# BIO_SENSOR.net
KiCad netlist of a schematic drawn in Altium Designer
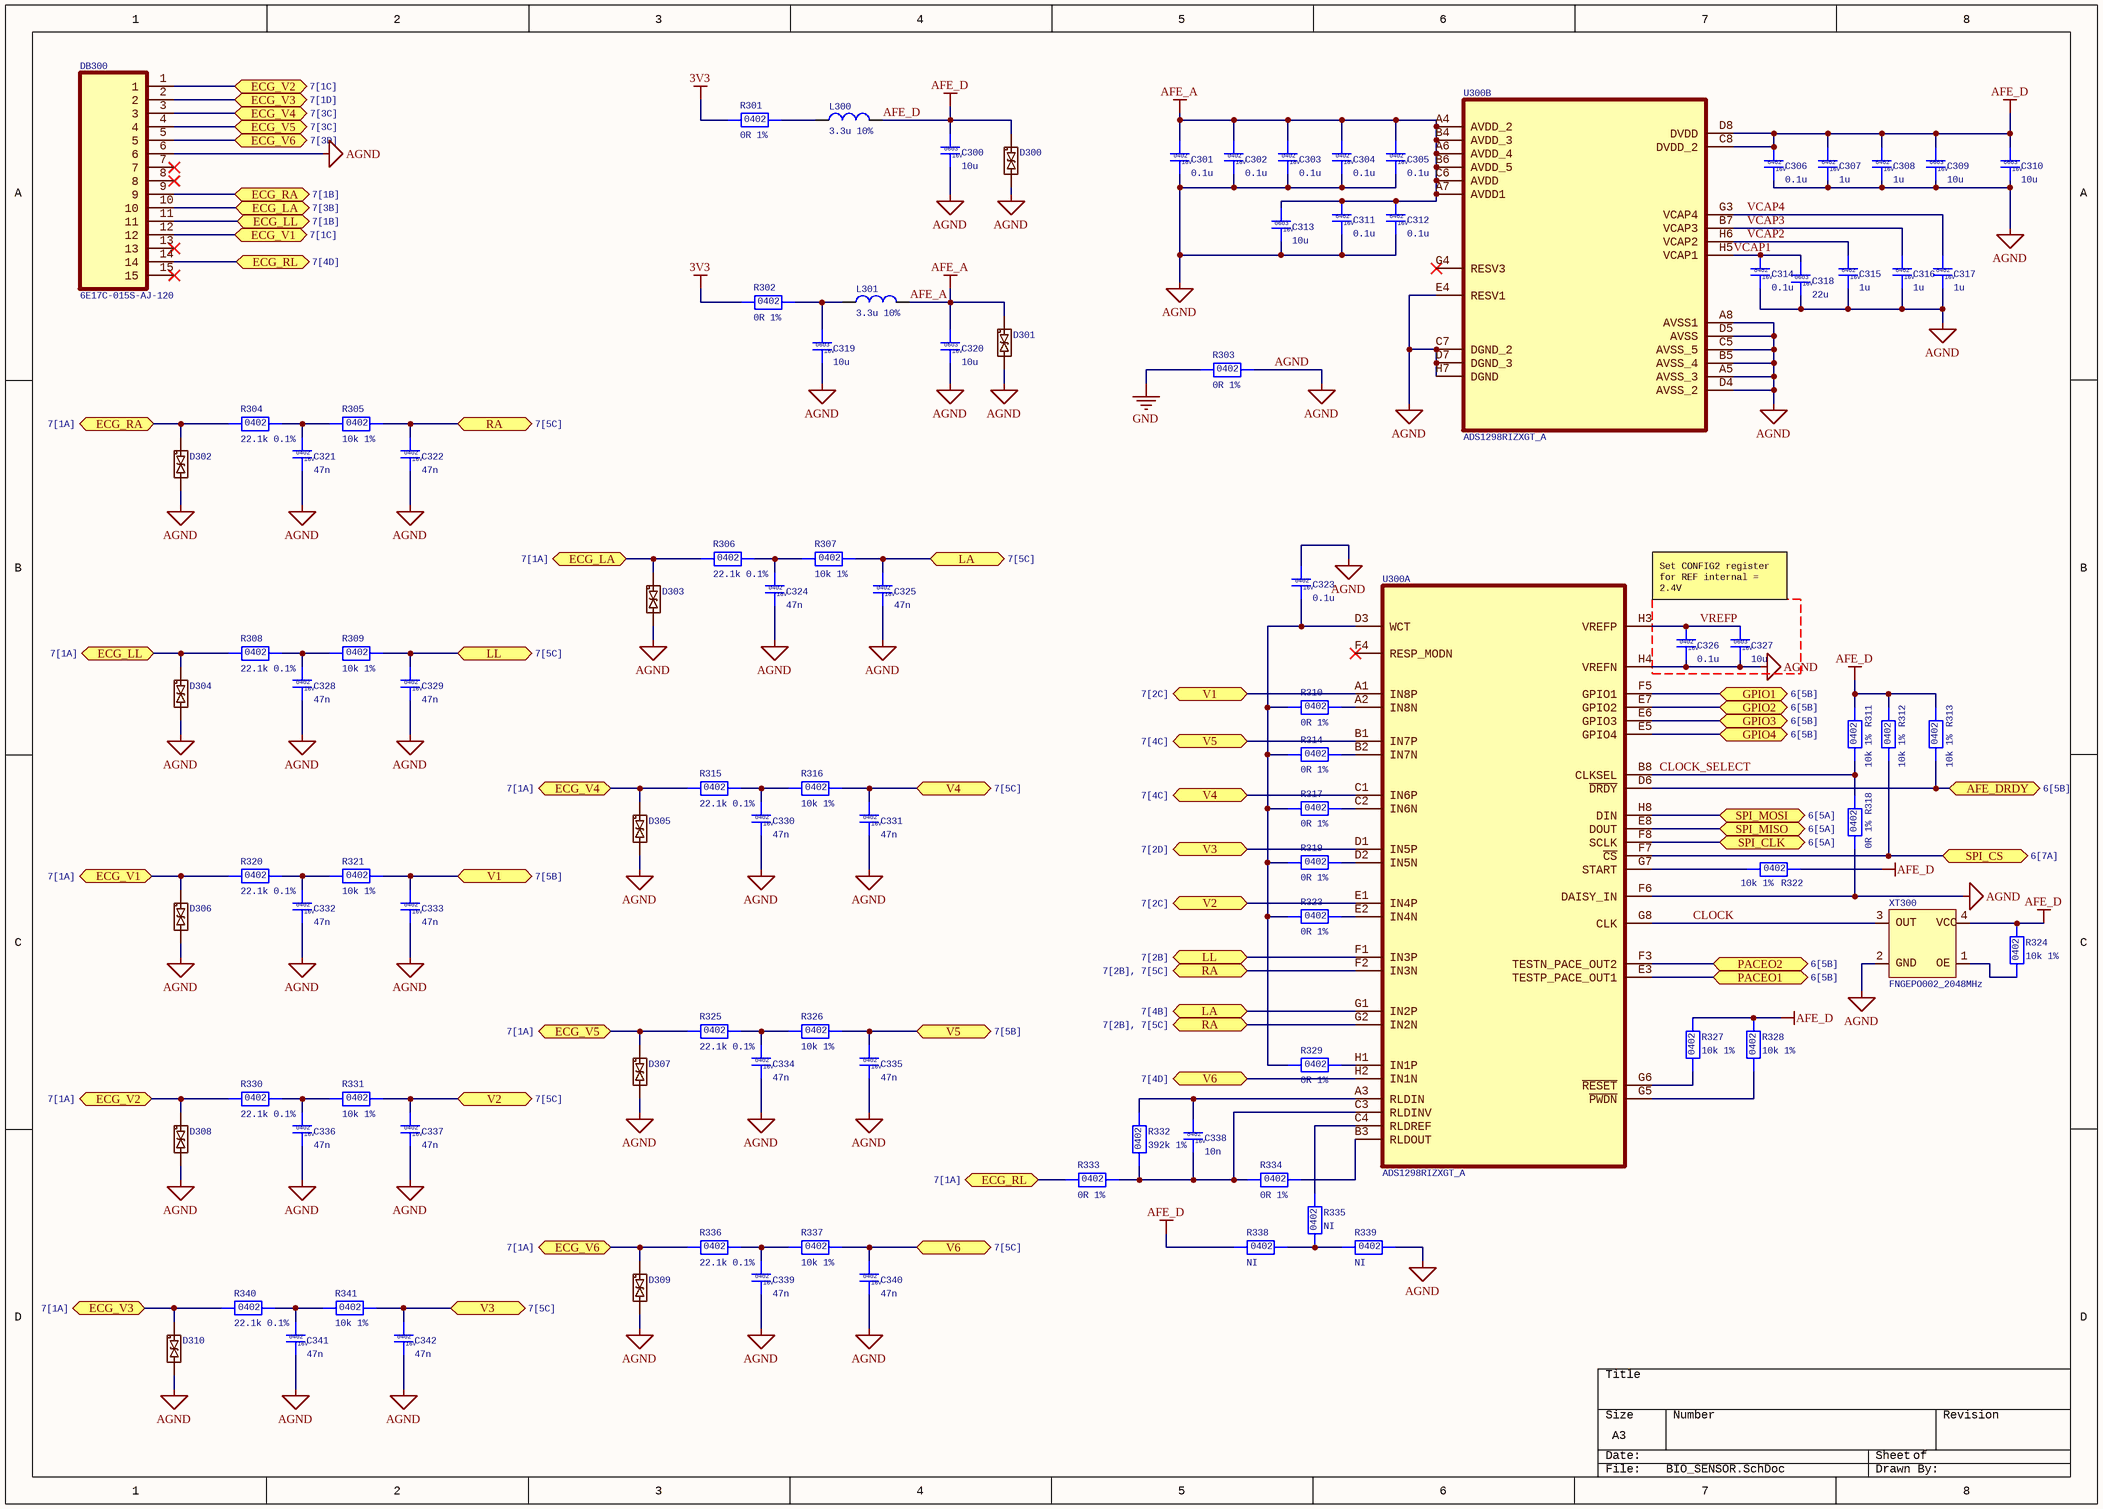
[diagram p0: BIO_SENSOR.SchDoc]

(export (version "E")
  (design (tool "Eeschema 10.0.6"))
  (components
    (comp (ref "C300")
      (value "10u")
      (footprint "CAP0603")
      (fields
        (field (name "MANUFACTURER") "Murata")
        (field (name "MANUFACTURER PART NUMBER") "GRT188R61C106ME13D")
      )
      (libsource (lib "Hw_Lib") (part "C_0402_10u"))
    )
    (comp (ref "C301")
      (value "0.1u")
      (footprint "CAP0402")
      (fields
        (field (name "MANUFACTURER") "Murata")
        (field (name "MANUFACTURER PART NUMBER") "GRM155R71C104KA88J")
      )
      (libsource (lib "Hw_Lib") (part "C_0402_0.1u"))
    )
    (comp (ref "C302")
      (value "0.1u")
      (footprint "CAP0402")
      (fields
        (field (name "MANUFACTURER") "Murata")
        (field (name "MANUFACTURER PART NUMBER") "GRM155R71C104KA88J")
      )
      (libsource (lib "Hw_Lib") (part "C_0402_0.1u"))
    )
    (comp (ref "C303")
      (value "0.1u")
      (footprint "CAP0402")
      (fields
        (field (name "MANUFACTURER") "Murata")
        (field (name "MANUFACTURER PART NUMBER") "GRM155R71C104KA88J")
      )
      (libsource (lib "Hw_Lib") (part "C_0402_0.1u"))
    )
    (comp (ref "C304")
      (value "0.1u")
      (footprint "CAP0402")
      (fields
        (field (name "MANUFACTURER") "Murata")
        (field (name "MANUFACTURER PART NUMBER") "GRM155R71C104KA88J")
      )
      (libsource (lib "Hw_Lib") (part "C_0402_0.1u"))
    )
    (comp (ref "C305")
      (value "0.1u")
      (footprint "CAP0402")
      (fields
        (field (name "MANUFACTURER") "Murata")
        (field (name "MANUFACTURER PART NUMBER") "GRM155R71C104KA88J")
      )
      (libsource (lib "Hw_Lib") (part "C_0402_0.1u"))
    )
    (comp (ref "C306")
      (value "0.1u")
      (footprint "CAP0402")
      (fields
        (field (name "MANUFACTURER") "Murata")
        (field (name "MANUFACTURER PART NUMBER") "GRM155R71C104KA88J")
      )
      (libsource (lib "Hw_Lib") (part "C_0402_0.1u"))
    )
    (comp (ref "C307")
      (value "1u")
      (footprint "CAP0402")
      (fields
        (field (name "MANUFACTURER") "Taiyo Yuden")
        (field (name "MANUFACTURER PART NUMBER") "EMK105BJ105KV-F")
      )
      (libsource (lib "Hw_Lib") (part "C_0402_1u"))
    )
    (comp (ref "C308")
      (value "1u")
      (footprint "CAP0402")
      (fields
        (field (name "MANUFACTURER") "Taiyo Yuden")
        (field (name "MANUFACTURER PART NUMBER") "EMK105BJ105KV-F")
      )
      (libsource (lib "Hw_Lib") (part "C_0402_1u"))
    )
    (comp (ref "C309")
      (value "10u")
      (footprint "CAP0603")
      (fields
        (field (name "MANUFACTURER") "Murata")
        (field (name "MANUFACTURER PART NUMBER") "GRT188R61C106ME13D")
      )
      (libsource (lib "Hw_Lib") (part "C_0402_10u"))
    )
    (comp (ref "C310")
      (value "10u")
      (footprint "CAP0603")
      (fields
        (field (name "MANUFACTURER") "Murata")
        (field (name "MANUFACTURER PART NUMBER") "GRT188R61C106ME13D")
      )
      (libsource (lib "Hw_Lib") (part "C_0402_10u"))
    )
    (comp (ref "C311")
      (value "0.1u")
      (footprint "CAP0402")
      (fields
        (field (name "MANUFACTURER") "Murata")
        (field (name "MANUFACTURER PART NUMBER") "GRM155R71C104KA88J")
      )
      (libsource (lib "Hw_Lib") (part "C_0402_0.1u"))
    )
    (comp (ref "C312")
      (value "0.1u")
      (footprint "CAP0402")
      (fields
        (field (name "MANUFACTURER") "Murata")
        (field (name "MANUFACTURER PART NUMBER") "GRM155R71C104KA88J")
      )
      (libsource (lib "Hw_Lib") (part "C_0402_0.1u"))
    )
    (comp (ref "C313")
      (value "10u")
      (footprint "CAP0603")
      (fields
        (field (name "MANUFACTURER") "Murata")
        (field (name "MANUFACTURER PART NUMBER") "GRT188R61C106ME13D")
      )
      (libsource (lib "Hw_Lib") (part "C_0402_10u"))
    )
    (comp (ref "C314")
      (value "0.1u")
      (footprint "CAP0402")
      (fields
        (field (name "MANUFACTURER") "Murata")
        (field (name "MANUFACTURER PART NUMBER") "GRM155R71C104KA88J")
      )
      (libsource (lib "Hw_Lib") (part "C_0402_0.1u"))
    )
    (comp (ref "C315")
      (value "1u")
      (footprint "CAP0402")
      (fields
        (field (name "MANUFACTURER") "Taiyo Yuden")
        (field (name "MANUFACTURER PART NUMBER") "EMK105BJ105KV-F")
      )
      (libsource (lib "Hw_Lib") (part "C_0402_1u"))
    )
    (comp (ref "C316")
      (value "1u")
      (footprint "CAP0402")
      (fields
        (field (name "MANUFACTURER") "Taiyo Yuden")
        (field (name "MANUFACTURER PART NUMBER") "EMK105BJ105KV-F")
      )
      (libsource (lib "Hw_Lib") (part "C_0402_1u"))
    )
    (comp (ref "C317")
      (value "1u")
      (footprint "CAP0402")
      (fields
        (field (name "MANUFACTURER") "Taiyo Yuden")
        (field (name "MANUFACTURER PART NUMBER") "EMK105BJ105KV-F")
      )
      (libsource (lib "Hw_Lib") (part "C_0402_1u"))
    )
    (comp (ref "C318")
      (value "22u")
      (footprint "CAP0603")
      (fields
        (field (name "MANUFACTURER") "Samsung")
        (field (name "MANUFACTURER PART NUMBER") "CL10A226MO7JZNC")
      )
      (libsource (lib "Hw_Lib") (part "C_0402_22u"))
    )
    (comp (ref "C319")
      (value "10u")
      (footprint "CAP0603")
      (fields
        (field (name "MANUFACTURER") "Murata")
        (field (name "MANUFACTURER PART NUMBER") "GRT188R61C106ME13D")
      )
      (libsource (lib "Hw_Lib") (part "C_0402_10u"))
    )
    (comp (ref "C320")
      (value "10u")
      (footprint "CAP0603")
      (fields
        (field (name "MANUFACTURER") "Murata")
        (field (name "MANUFACTURER PART NUMBER") "GRT188R61C106ME13D")
      )
      (libsource (lib "Hw_Lib") (part "C_0402_10u"))
    )
    (comp (ref "C321")
      (value "47n")
      (footprint "CAP0402")
      (fields
        (field (name "MANUFACTURER") "Murata")
        (field (name "MANUFACTURER PART NUMBER") "GCM155R71C473KA37D")
      )
      (libsource (lib "Hw_Lib") (part "C_0402_47n"))
    )
    (comp (ref "C322")
      (value "47n")
      (footprint "CAP0402")
      (fields
        (field (name "MANUFACTURER") "Murata")
        (field (name "MANUFACTURER PART NUMBER") "GCM155R71C473KA37D")
      )
      (libsource (lib "Hw_Lib") (part "C_0402_47n"))
    )
    (comp (ref "C323")
      (value "0.1u")
      (footprint "CAP0402")
      (fields
        (field (name "MANUFACTURER") "Murata")
        (field (name "MANUFACTURER PART NUMBER") "GRM155R71C104KA88J")
      )
      (libsource (lib "Hw_Lib") (part "C_0402_0.1u"))
    )
    (comp (ref "C324")
      (value "47n")
      (footprint "CAP0402")
      (fields
        (field (name "MANUFACTURER") "Murata")
        (field (name "MANUFACTURER PART NUMBER") "GCM155R71C473KA37D")
      )
      (libsource (lib "Hw_Lib") (part "C_0402_47n"))
    )
    (comp (ref "C325")
      (value "47n")
      (footprint "CAP0402")
      (fields
        (field (name "MANUFACTURER") "Murata")
        (field (name "MANUFACTURER PART NUMBER") "GCM155R71C473KA37D")
      )
      (libsource (lib "Hw_Lib") (part "C_0402_47n"))
    )
    (comp (ref "C326")
      (value "0.1u")
      (footprint "CAP0402")
      (fields
        (field (name "MANUFACTURER") "Murata")
        (field (name "MANUFACTURER PART NUMBER") "GRM155R71C104KA88J")
      )
      (libsource (lib "Hw_Lib") (part "C_0402_0.1u"))
    )
    (comp (ref "C327")
      (value "10u")
      (footprint "CAP0603")
      (fields
        (field (name "MANUFACTURER") "Murata")
        (field (name "MANUFACTURER PART NUMBER") "GRT188R61C106ME13D")
      )
      (libsource (lib "Hw_Lib") (part "C_0402_10u"))
    )
    (comp (ref "C328")
      (value "47n")
      (footprint "CAP0402")
      (fields
        (field (name "MANUFACTURER") "Murata")
        (field (name "MANUFACTURER PART NUMBER") "GCM155R71C473KA37D")
      )
      (libsource (lib "Hw_Lib") (part "C_0402_47n"))
    )
    (comp (ref "C329")
      (value "47n")
      (footprint "CAP0402")
      (fields
        (field (name "MANUFACTURER") "Murata")
        (field (name "MANUFACTURER PART NUMBER") "GCM155R71C473KA37D")
      )
      (libsource (lib "Hw_Lib") (part "C_0402_47n"))
    )
    (comp (ref "C330")
      (value "47n")
      (footprint "CAP0402")
      (fields
        (field (name "MANUFACTURER") "Murata")
        (field (name "MANUFACTURER PART NUMBER") "GCM155R71C473KA37D")
      )
      (libsource (lib "Hw_Lib") (part "C_0402_47n"))
    )
    (comp (ref "C331")
      (value "47n")
      (footprint "CAP0402")
      (fields
        (field (name "MANUFACTURER") "Murata")
        (field (name "MANUFACTURER PART NUMBER") "GCM155R71C473KA37D")
      )
      (libsource (lib "Hw_Lib") (part "C_0402_47n"))
    )
    (comp (ref "C332")
      (value "47n")
      (footprint "CAP0402")
      (fields
        (field (name "MANUFACTURER") "Murata")
        (field (name "MANUFACTURER PART NUMBER") "GCM155R71C473KA37D")
      )
      (libsource (lib "Hw_Lib") (part "C_0402_47n"))
    )
    (comp (ref "C333")
      (value "47n")
      (footprint "CAP0402")
      (fields
        (field (name "MANUFACTURER") "Murata")
        (field (name "MANUFACTURER PART NUMBER") "GCM155R71C473KA37D")
      )
      (libsource (lib "Hw_Lib") (part "C_0402_47n"))
    )
    (comp (ref "C334")
      (value "47n")
      (footprint "CAP0402")
      (fields
        (field (name "MANUFACTURER") "Murata")
        (field (name "MANUFACTURER PART NUMBER") "GCM155R71C473KA37D")
      )
      (libsource (lib "Hw_Lib") (part "C_0402_47n"))
    )
    (comp (ref "C335")
      (value "47n")
      (footprint "CAP0402")
      (fields
        (field (name "MANUFACTURER") "Murata")
        (field (name "MANUFACTURER PART NUMBER") "GCM155R71C473KA37D")
      )
      (libsource (lib "Hw_Lib") (part "C_0402_47n"))
    )
    (comp (ref "C336")
      (value "47n")
      (footprint "CAP0402")
      (fields
        (field (name "MANUFACTURER") "Murata")
        (field (name "MANUFACTURER PART NUMBER") "GCM155R71C473KA37D")
      )
      (libsource (lib "Hw_Lib") (part "C_0402_47n"))
    )
    (comp (ref "C337")
      (value "47n")
      (footprint "CAP0402")
      (fields
        (field (name "MANUFACTURER") "Murata")
        (field (name "MANUFACTURER PART NUMBER") "GCM155R71C473KA37D")
      )
      (libsource (lib "Hw_Lib") (part "C_0402_47n"))
    )
    (comp (ref "C338")
      (value "10n")
      (footprint "CAP0402")
      (fields
        (field (name "MANUFACTURER") "Murata")
        (field (name "MANUFACTURER PART NUMBER") "GRM155R71C103KA01D")
      )
      (libsource (lib "Hw_Lib") (part "C_0402_10n"))
    )
    (comp (ref "C339")
      (value "47n")
      (footprint "CAP0402")
      (fields
        (field (name "MANUFACTURER") "Murata")
        (field (name "MANUFACTURER PART NUMBER") "GCM155R71C473KA37D")
      )
      (libsource (lib "Hw_Lib") (part "C_0402_47n"))
    )
    (comp (ref "C340")
      (value "47n")
      (footprint "CAP0402")
      (fields
        (field (name "MANUFACTURER") "Murata")
        (field (name "MANUFACTURER PART NUMBER") "GCM155R71C473KA37D")
      )
      (libsource (lib "Hw_Lib") (part "C_0402_47n"))
    )
    (comp (ref "C341")
      (value "47n")
      (footprint "CAP0402")
      (fields
        (field (name "MANUFACTURER") "Murata")
        (field (name "MANUFACTURER PART NUMBER") "GCM155R71C473KA37D")
      )
      (libsource (lib "Hw_Lib") (part "C_0402_47n"))
    )
    (comp (ref "C342")
      (value "47n")
      (footprint "CAP0402")
      (fields
        (field (name "MANUFACTURER") "Murata")
        (field (name "MANUFACTURER PART NUMBER") "GCM155R71C473KA37D")
      )
      (libsource (lib "Hw_Lib") (part "C_0402_47n"))
    )
    (comp (ref "D300")
      (value "DESD3V3S1BL-7B")
      (footprint "DESD3V3S1BL-7B")
      (description "Trans Voltage Suppressor Diode, 35W, 3.3V V(RWM), Bidirectional, 1 Element, Silicon")
      (fields (field (name "MANUFACTURER") "Diodes"))
      (libsource (lib "Hw_Lib") (part "DESD3V3S1BL-7B"))
    )
    (comp (ref "D301")
      (value "DESD3V3S1BL-7B")
      (footprint "DESD3V3S1BL-7B")
      (description "Trans Voltage Suppressor Diode, 35W, 3.3V V(RWM), Bidirectional, 1 Element, Silicon")
      (fields (field (name "MANUFACTURER") "Diodes"))
      (libsource (lib "Hw_Lib") (part "DESD3V3S1BL-7B"))
    )
    (comp (ref "D302")
      (value "DESD3V3S1BL-7B")
      (footprint "DESD3V3S1BL-7B")
      (description "Trans Voltage Suppressor Diode, 35W, 3.3V V(RWM), Bidirectional, 1 Element, Silicon")
      (fields (field (name "MANUFACTURER") "Diodes"))
      (libsource (lib "Hw_Lib") (part "DESD3V3S1BL-7B"))
    )
    (comp (ref "D303")
      (value "DESD3V3S1BL-7B")
      (footprint "DESD3V3S1BL-7B")
      (description "Trans Voltage Suppressor Diode, 35W, 3.3V V(RWM), Bidirectional, 1 Element, Silicon")
      (fields (field (name "MANUFACTURER") "Diodes"))
      (libsource (lib "Hw_Lib") (part "DESD3V3S1BL-7B"))
    )
    (comp (ref "D304")
      (value "DESD3V3S1BL-7B")
      (footprint "DESD3V3S1BL-7B")
      (description "Trans Voltage Suppressor Diode, 35W, 3.3V V(RWM), Bidirectional, 1 Element, Silicon")
      (fields (field (name "MANUFACTURER") "Diodes"))
      (libsource (lib "Hw_Lib") (part "DESD3V3S1BL-7B"))
    )
    (comp (ref "D305")
      (value "DESD3V3S1BL-7B")
      (footprint "DESD3V3S1BL-7B")
      (description "Trans Voltage Suppressor Diode, 35W, 3.3V V(RWM), Bidirectional, 1 Element, Silicon")
      (fields (field (name "MANUFACTURER") "Diodes"))
      (libsource (lib "Hw_Lib") (part "DESD3V3S1BL-7B"))
    )
    (comp (ref "D306")
      (value "DESD3V3S1BL-7B")
      (footprint "DESD3V3S1BL-7B")
      (description "Trans Voltage Suppressor Diode, 35W, 3.3V V(RWM), Bidirectional, 1 Element, Silicon")
      (fields (field (name "MANUFACTURER") "Diodes"))
      (libsource (lib "Hw_Lib") (part "DESD3V3S1BL-7B"))
    )
    (comp (ref "D307")
      (value "DESD3V3S1BL-7B")
      (footprint "DESD3V3S1BL-7B")
      (description "Trans Voltage Suppressor Diode, 35W, 3.3V V(RWM), Bidirectional, 1 Element, Silicon")
      (fields (field (name "MANUFACTURER") "Diodes"))
      (libsource (lib "Hw_Lib") (part "DESD3V3S1BL-7B"))
    )
    (comp (ref "D308")
      (value "DESD3V3S1BL-7B")
      (footprint "DESD3V3S1BL-7B")
      (description "Trans Voltage Suppressor Diode, 35W, 3.3V V(RWM), Bidirectional, 1 Element, Silicon")
      (fields (field (name "MANUFACTURER") "Diodes"))
      (libsource (lib "Hw_Lib") (part "DESD3V3S1BL-7B"))
    )
    (comp (ref "D309")
      (value "DESD3V3S1BL-7B")
      (footprint "DESD3V3S1BL-7B")
      (description "Trans Voltage Suppressor Diode, 35W, 3.3V V(RWM), Bidirectional, 1 Element, Silicon")
      (fields (field (name "MANUFACTURER") "Diodes"))
      (libsource (lib "Hw_Lib") (part "DESD3V3S1BL-7B"))
    )
    (comp (ref "D310")
      (value "DESD3V3S1BL-7B")
      (footprint "DESD3V3S1BL-7B")
      (description "Trans Voltage Suppressor Diode, 35W, 3.3V V(RWM), Bidirectional, 1 Element, Silicon")
      (fields (field (name "MANUFACTURER") "Diodes"))
      (libsource (lib "Hw_Lib") (part "DESD3V3S1BL-7B"))
    )
    (comp (ref "DB300")
      (value "6E17C-015S-AJ-120")
      (footprint "6E17C-015S-AJ-120")
      (description "Conn D-Subminiature SKT 15 POS 2.74mm Solder RA Thru-Hole 15 Terminal 1 Port")
      (fields
        (field (name "MANUFACTURER") "Amphenol Communications Solutions")
        (field (name "MANUFACTURER PART NUMBER") "6E17C015SAJ120")
      )
      (libsource (lib "Hw_Lib") (part "6E17C-015S-AJ-120"))
    )
    (comp (ref "L300")
      (value "3.3u 10%")
      (footprint "0402(1005)")
      (description "General Purpose Inductor, 2.7uH, 10%, 1 Element, Ferrite-Core, SMD, 0402")
      (fields
        (field (name "MANUFACTURER") "Abracon")
        (field (name "MANUFACTURER PART NUMBER") "AIML-0402-2R7K-T")
      )
      (libsource (lib "Hw_Lib") (part "Inductor 3.3u"))
    )
    (comp (ref "L301")
      (value "3.3u 10%")
      (footprint "0402(1005)")
      (description "General Purpose Inductor, 2.7uH, 10%, 1 Element, Ferrite-Core, SMD, 0402")
      (fields
        (field (name "MANUFACTURER") "Abracon")
        (field (name "MANUFACTURER PART NUMBER") "AIML-0402-2R7K-T")
      )
      (libsource (lib "Hw_Lib") (part "Inductor 3.3u"))
    )
    (comp (ref "R301")
      (value "0R 1%")
      (footprint "RES0402")
      (description "Metal Glaze/thick Film, 0.0625W, 0ohm, Surface Mount, 0402")
      (fields
        (field (name "MANUFACTURER") "Yageo")
        (field (name "MANUFACTURER PART NUMBER") "RC0402JR-070RL")
      )
      (libsource (lib "Hw_Lib") (part "R_0402_0R"))
    )
    (comp (ref "R302")
      (value "0R 1%")
      (footprint "RES0402")
      (description "Metal Glaze/thick Film, 0.0625W, 0ohm, Surface Mount, 0402")
      (fields
        (field (name "MANUFACTURER") "Yageo")
        (field (name "MANUFACTURER PART NUMBER") "RC0402JR-070RL")
      )
      (libsource (lib "Hw_Lib") (part "R_0402_0R"))
    )
    (comp (ref "R303")
      (value "0R 1%")
      (footprint "RES0402")
      (description "Metal Glaze/thick Film, 0.0625W, 0ohm, Surface Mount, 0402")
      (fields
        (field (name "MANUFACTURER") "Yageo")
        (field (name "MANUFACTURER PART NUMBER") "RC0402JR-070RL")
      )
      (libsource (lib "Hw_Lib") (part "R_0402_0R"))
    )
    (comp (ref "R304")
      (value "22.1k 0.1%")
      (footprint "R0402")
      (description "Fixed Resistor, Thin Film, 0.063W, 22100ohm, 50V, 0.1% +/-Tol, 25ppm/Cel, Surface Mount, 0402")
      (fields
        (field (name "MANUFACTURER") "Vishay Dale")
        (field (name "MANUFACTURER PART NUMBER") "TNPW040222K1BEED")
      )
      (libsource (lib "Hw_Lib") (part "R_0402_22.1k"))
    )
    (comp (ref "R305")
      (value "10k 1%")
      (footprint "R0402")
      (fields
        (field (name "MANUFACTURER") "Samsung")
        (field (name "MANUFACTURER PART NUMBER") "RC1005F103CS")
        (field (name "TOLERANCE") "1%")
      )
      (libsource (lib "Hw_Lib") (part "R_0402_10k"))
    )
    (comp (ref "R306")
      (value "22.1k 0.1%")
      (footprint "R0402")
      (description "Fixed Resistor, Thin Film, 0.063W, 22100ohm, 50V, 0.1% +/-Tol, 25ppm/Cel, Surface Mount, 0402")
      (fields
        (field (name "MANUFACTURER") "Vishay Dale")
        (field (name "MANUFACTURER PART NUMBER") "TNPW040222K1BEED")
      )
      (libsource (lib "Hw_Lib") (part "R_0402_22.1k"))
    )
    (comp (ref "R307")
      (value "10k 1%")
      (footprint "R0402")
      (fields
        (field (name "MANUFACTURER") "Samsung")
        (field (name "MANUFACTURER PART NUMBER") "RC1005F103CS")
        (field (name "TOLERANCE") "1%")
      )
      (libsource (lib "Hw_Lib") (part "R_0402_10k"))
    )
    (comp (ref "R308")
      (value "22.1k 0.1%")
      (footprint "R0402")
      (description "Fixed Resistor, Thin Film, 0.063W, 22100ohm, 50V, 0.1% +/-Tol, 25ppm/Cel, Surface Mount, 0402")
      (fields
        (field (name "MANUFACTURER") "Vishay Dale")
        (field (name "MANUFACTURER PART NUMBER") "TNPW040222K1BEED")
      )
      (libsource (lib "Hw_Lib") (part "R_0402_22.1k"))
    )
    (comp (ref "R309")
      (value "10k 1%")
      (footprint "R0402")
      (fields
        (field (name "MANUFACTURER") "Samsung")
        (field (name "MANUFACTURER PART NUMBER") "RC1005F103CS")
        (field (name "TOLERANCE") "1%")
      )
      (libsource (lib "Hw_Lib") (part "R_0402_10k"))
    )
    (comp (ref "R310")
      (value "0R 1%")
      (footprint "RES0402")
      (description "Metal Glaze/thick Film, 0.0625W, 0ohm, Surface Mount, 0402")
      (fields
        (field (name "MANUFACTURER") "Yageo")
        (field (name "MANUFACTURER PART NUMBER") "RC0402JR-070RL")
      )
      (libsource (lib "Hw_Lib") (part "R_0402_0R"))
    )
    (comp (ref "R311")
      (value "10k 1%")
      (footprint "R0402")
      (fields
        (field (name "MANUFACTURER") "Samsung")
        (field (name "MANUFACTURER PART NUMBER") "RC1005F103CS")
        (field (name "TOLERANCE") "1%")
      )
      (libsource (lib "Hw_Lib") (part "R_0402_10k"))
    )
    (comp (ref "R312")
      (value "10k 1%")
      (footprint "R0402")
      (fields
        (field (name "MANUFACTURER") "Samsung")
        (field (name "MANUFACTURER PART NUMBER") "RC1005F103CS")
        (field (name "TOLERANCE") "1%")
      )
      (libsource (lib "Hw_Lib") (part "R_0402_10k"))
    )
    (comp (ref "R313")
      (value "10k 1%")
      (footprint "R0402")
      (fields
        (field (name "MANUFACTURER") "Samsung")
        (field (name "MANUFACTURER PART NUMBER") "RC1005F103CS")
        (field (name "TOLERANCE") "1%")
      )
      (libsource (lib "Hw_Lib") (part "R_0402_10k"))
    )
    (comp (ref "R314")
      (value "0R 1%")
      (footprint "RES0402")
      (description "Metal Glaze/thick Film, 0.0625W, 0ohm, Surface Mount, 0402")
      (fields
        (field (name "MANUFACTURER") "Yageo")
        (field (name "MANUFACTURER PART NUMBER") "RC0402JR-070RL")
      )
      (libsource (lib "Hw_Lib") (part "R_0402_0R"))
    )
    (comp (ref "R315")
      (value "22.1k 0.1%")
      (footprint "R0402")
      (description "Fixed Resistor, Thin Film, 0.063W, 22100ohm, 50V, 0.1% +/-Tol, 25ppm/Cel, Surface Mount, 0402")
      (fields
        (field (name "MANUFACTURER") "Vishay Dale")
        (field (name "MANUFACTURER PART NUMBER") "TNPW040222K1BEED")
      )
      (libsource (lib "Hw_Lib") (part "R_0402_22.1k"))
    )
    (comp (ref "R316")
      (value "10k 1%")
      (footprint "R0402")
      (fields
        (field (name "MANUFACTURER") "Samsung")
        (field (name "MANUFACTURER PART NUMBER") "RC1005F103CS")
        (field (name "TOLERANCE") "1%")
      )
      (libsource (lib "Hw_Lib") (part "R_0402_10k"))
    )
    (comp (ref "R317")
      (value "0R 1%")
      (footprint "RES0402")
      (description "Metal Glaze/thick Film, 0.0625W, 0ohm, Surface Mount, 0402")
      (fields
        (field (name "MANUFACTURER") "Yageo")
        (field (name "MANUFACTURER PART NUMBER") "RC0402JR-070RL")
      )
      (libsource (lib "Hw_Lib") (part "R_0402_0R"))
    )
    (comp (ref "R318")
      (value "0R 1%")
      (footprint "RES0402")
      (description "Metal Glaze/thick Film, 0.0625W, 0ohm, Surface Mount, 0402")
      (fields
        (field (name "MANUFACTURER") "Yageo")
        (field (name "MANUFACTURER PART NUMBER") "RC0402JR-070RL")
      )
      (libsource (lib "Hw_Lib") (part "R_0402_0R"))
    )
    (comp (ref "R319")
      (value "0R 1%")
      (footprint "RES0402")
      (description "Metal Glaze/thick Film, 0.0625W, 0ohm, Surface Mount, 0402")
      (fields
        (field (name "MANUFACTURER") "Yageo")
        (field (name "MANUFACTURER PART NUMBER") "RC0402JR-070RL")
      )
      (libsource (lib "Hw_Lib") (part "R_0402_0R"))
    )
    (comp (ref "R320")
      (value "22.1k 0.1%")
      (footprint "R0402")
      (description "Fixed Resistor, Thin Film, 0.063W, 22100ohm, 50V, 0.1% +/-Tol, 25ppm/Cel, Surface Mount, 0402")
      (fields
        (field (name "MANUFACTURER") "Vishay Dale")
        (field (name "MANUFACTURER PART NUMBER") "TNPW040222K1BEED")
      )
      (libsource (lib "Hw_Lib") (part "R_0402_22.1k"))
    )
    (comp (ref "R321")
      (value "10k 1%")
      (footprint "R0402")
      (fields
        (field (name "MANUFACTURER") "Samsung")
        (field (name "MANUFACTURER PART NUMBER") "RC1005F103CS")
        (field (name "TOLERANCE") "1%")
      )
      (libsource (lib "Hw_Lib") (part "R_0402_10k"))
    )
    (comp (ref "R322")
      (value "10k 1%")
      (footprint "R0402")
      (fields
        (field (name "MANUFACTURER") "Samsung")
        (field (name "MANUFACTURER PART NUMBER") "RC1005F103CS")
        (field (name "TOLERANCE") "1%")
      )
      (libsource (lib "Hw_Lib") (part "R_0402_10k"))
    )
    (comp (ref "R323")
      (value "0R 1%")
      (footprint "RES0402")
      (description "Metal Glaze/thick Film, 0.0625W, 0ohm, Surface Mount, 0402")
      (fields
        (field (name "MANUFACTURER") "Yageo")
        (field (name "MANUFACTURER PART NUMBER") "RC0402JR-070RL")
      )
      (libsource (lib "Hw_Lib") (part "R_0402_0R"))
    )
    (comp (ref "R324")
      (value "10k 1%")
      (footprint "R0402")
      (fields
        (field (name "MANUFACTURER") "Samsung")
        (field (name "MANUFACTURER PART NUMBER") "RC1005F103CS")
        (field (name "TOLERANCE") "1%")
      )
      (libsource (lib "Hw_Lib") (part "R_0402_10k"))
    )
    (comp (ref "R325")
      (value "22.1k 0.1%")
      (footprint "R0402")
      (description "Fixed Resistor, Thin Film, 0.063W, 22100ohm, 50V, 0.1% +/-Tol, 25ppm/Cel, Surface Mount, 0402")
      (fields
        (field (name "MANUFACTURER") "Vishay Dale")
        (field (name "MANUFACTURER PART NUMBER") "TNPW040222K1BEED")
      )
      (libsource (lib "Hw_Lib") (part "R_0402_22.1k"))
    )
    (comp (ref "R326")
      (value "10k 1%")
      (footprint "R0402")
      (fields
        (field (name "MANUFACTURER") "Samsung")
        (field (name "MANUFACTURER PART NUMBER") "RC1005F103CS")
        (field (name "TOLERANCE") "1%")
      )
      (libsource (lib "Hw_Lib") (part "R_0402_10k"))
    )
    (comp (ref "R327")
      (value "10k 1%")
      (footprint "R0402")
      (fields
        (field (name "MANUFACTURER") "Samsung")
        (field (name "MANUFACTURER PART NUMBER") "RC1005F103CS")
        (field (name "TOLERANCE") "1%")
      )
      (libsource (lib "Hw_Lib") (part "R_0402_10k"))
    )
    (comp (ref "R328")
      (value "10k 1%")
      (footprint "R0402")
      (fields
        (field (name "MANUFACTURER") "Samsung")
        (field (name "MANUFACTURER PART NUMBER") "RC1005F103CS")
        (field (name "TOLERANCE") "1%")
      )
      (libsource (lib "Hw_Lib") (part "R_0402_10k"))
    )
    (comp (ref "R329")
      (value "0R 1%")
      (footprint "RES0402")
      (description "Metal Glaze/thick Film, 0.0625W, 0ohm, Surface Mount, 0402")
      (fields
        (field (name "MANUFACTURER") "Yageo")
        (field (name "MANUFACTURER PART NUMBER") "RC0402JR-070RL")
      )
      (libsource (lib "Hw_Lib") (part "R_0402_0R"))
    )
    (comp (ref "R330")
      (value "22.1k 0.1%")
      (footprint "R0402")
      (description "Fixed Resistor, Thin Film, 0.063W, 22100ohm, 50V, 0.1% +/-Tol, 25ppm/Cel, Surface Mount, 0402")
      (fields
        (field (name "MANUFACTURER") "Vishay Dale")
        (field (name "MANUFACTURER PART NUMBER") "TNPW040222K1BEED")
      )
      (libsource (lib "Hw_Lib") (part "R_0402_22.1k"))
    )
    (comp (ref "R331")
      (value "10k 1%")
      (footprint "R0402")
      (fields
        (field (name "MANUFACTURER") "Samsung")
        (field (name "MANUFACTURER PART NUMBER") "RC1005F103CS")
        (field (name "TOLERANCE") "1%")
      )
      (libsource (lib "Hw_Lib") (part "R_0402_10k"))
    )
    (comp (ref "R332")
      (value "392k 1%")
      (footprint "R0402")
      (fields
        (field (name "MANUFACTURER") "KOA Speer")
        (field (name "MANUFACTURER PART NUMBER") "RK73H1ETTP3923F")
        (field (name "TOLERANCE") "1%")
      )
      (libsource (lib "Hw_Lib") (part "R_0402_392k"))
    )
    (comp (ref "R333")
      (value "0R 1%")
      (footprint "RES0402")
      (description "Metal Glaze/thick Film, 0.0625W, 0ohm, Surface Mount, 0402")
      (fields
        (field (name "MANUFACTURER") "Yageo")
        (field (name "MANUFACTURER PART NUMBER") "RC0402JR-070RL")
      )
      (libsource (lib "Hw_Lib") (part "R_0402_0R"))
    )
    (comp (ref "R334")
      (value "0R 1%")
      (footprint "RES0402")
      (description "Metal Glaze/thick Film, 0.0625W, 0ohm, Surface Mount, 0402")
      (fields
        (field (name "MANUFACTURER") "Yageo")
        (field (name "MANUFACTURER PART NUMBER") "RC0402JR-070RL")
      )
      (libsource (lib "Hw_Lib") (part "R_0402_0R"))
    )
    (comp (ref "R335")
      (value "NI")
      (footprint "RES0402")
      (description "Metal Glaze/thick Film, 0.0625W, 0ohm, Surface Mount, 0402")
      (fields
        (field (name "MANUFACTURER") "Yageo")
        (field (name "MANUFACTURER PART NUMBER") "RC0402JR-070RL")
      )
      (libsource (lib "Hw_Lib") (part "R_0402_0R"))
    )
    (comp (ref "R336")
      (value "22.1k 0.1%")
      (footprint "R0402")
      (description "Fixed Resistor, Thin Film, 0.063W, 22100ohm, 50V, 0.1% +/-Tol, 25ppm/Cel, Surface Mount, 0402")
      (fields
        (field (name "MANUFACTURER") "Vishay Dale")
        (field (name "MANUFACTURER PART NUMBER") "TNPW040222K1BEED")
      )
      (libsource (lib "Hw_Lib") (part "R_0402_22.1k"))
    )
    (comp (ref "R337")
      (value "10k 1%")
      (footprint "R0402")
      (fields
        (field (name "MANUFACTURER") "Samsung")
        (field (name "MANUFACTURER PART NUMBER") "RC1005F103CS")
        (field (name "TOLERANCE") "1%")
      )
      (libsource (lib "Hw_Lib") (part "R_0402_10k"))
    )
    (comp (ref "R338")
      (value "NI")
      (footprint "RES0402")
      (description "Metal Glaze/thick Film, 0.0625W, 0ohm, Surface Mount, 0402")
      (fields
        (field (name "MANUFACTURER") "Yageo")
        (field (name "MANUFACTURER PART NUMBER") "RC0402JR-070RL")
      )
      (libsource (lib "Hw_Lib") (part "R_0402_0R"))
    )
    (comp (ref "R339")
      (value "NI")
      (footprint "RES0402")
      (description "Metal Glaze/thick Film, 0.0625W, 0ohm, Surface Mount, 0402")
      (fields
        (field (name "MANUFACTURER") "Yageo")
        (field (name "MANUFACTURER PART NUMBER") "RC0402JR-070RL")
      )
      (libsource (lib "Hw_Lib") (part "R_0402_0R"))
    )
    (comp (ref "R340")
      (value "22.1k 0.1%")
      (footprint "R0402")
      (description "Fixed Resistor, Thin Film, 0.063W, 22100ohm, 50V, 0.1% +/-Tol, 25ppm/Cel, Surface Mount, 0402")
      (fields
        (field (name "MANUFACTURER") "Vishay Dale")
        (field (name "MANUFACTURER PART NUMBER") "TNPW040222K1BEED")
      )
      (libsource (lib "Hw_Lib") (part "R_0402_22.1k"))
    )
    (comp (ref "R341")
      (value "10k 1%")
      (footprint "R0402")
      (fields
        (field (name "MANUFACTURER") "Samsung")
        (field (name "MANUFACTURER PART NUMBER") "RC1005F103CS")
        (field (name "TOLERANCE") "1%")
      )
      (libsource (lib "Hw_Lib") (part "R_0402_10k"))
    )
    (comp (ref "U300")
      (value "ADS1298RIZXGT_A")
      (footprint "ADS1298RIZXGT")
      (description "Analog Circuit, 1 Func, 8 Channel, PBGA64")
      (fields
        (field (name "MANUFACTURER") "Texas Instruments")
        (field (name "MANUFACTURER PART NUMBER") "ADS1298RIZXGT")
      )
      (libsource (lib "Hw_Lib") (part "ADS1298RIZXGT_A"))
    )
    (comp (ref "XT300")
      (value "FNGEPO002_2048MHz")
      (footprint "FNGEPO002")
      (description "CMOS Output Clock Oscillator, 2.048MHz Nom")
      (fields (field (name "MANUFACTURER") "Diodes") (field (name "MANUFACTURER PART NUMBER") "FNGEPO002"))
      (libsource (lib "Hw_Lib") (part "FNGEPO002_2048MHz"))
    )
  )
  (nets
    (net (code "2") (name "/AFE_DRDY") (class "Default")
      (node (ref "R313") (pin "1") (pinfunction "1_1") (pintype "passive"))
      (node (ref "U300") (pin "D6") (pinfunction "~{DRDY}_D6") (pintype "open_collector"))
    )
    (net (code "3") (name "/CLOCK") (class "Default")
      (node (ref "U300") (pin "G8") (pinfunction "CLK_G8") (pintype "open_collector"))
      (node (ref "XT300") (pin "3") (pinfunction "OUT_3") (pintype "passive"))
    )
    (net (code "4") (name "/CLOCK_SELECT") (class "Default")
      (node (ref "R311") (pin "1") (pinfunction "1_1") (pintype "passive"))
      (node (ref "R318") (pin "2") (pinfunction "2_2") (pintype "passive"))
      (node (ref "U300") (pin "B8") (pinfunction "CLKSEL_B8") (pintype "open_collector"))
    )
    (net (code "5") (name "/ECG_LA") (class "Default")
      (node (ref "D303") (pin "1") (pinfunction "1_1") (pintype "passive"))
      (node (ref "DB300") (pin "10") (pinfunction "10_10") (pintype "passive"))
      (node (ref "R306") (pin "1") (pinfunction "1_1") (pintype "passive"))
    )
    (net (code "6") (name "/ECG_LL") (class "Default")
      (node (ref "D304") (pin "1") (pinfunction "1_1") (pintype "passive"))
      (node (ref "DB300") (pin "11") (pinfunction "11_11") (pintype "passive"))
      (node (ref "R308") (pin "1") (pinfunction "1_1") (pintype "passive"))
    )
    (net (code "7") (name "/ECG_RA") (class "Default")
      (node (ref "D302") (pin "1") (pinfunction "1_1") (pintype "passive"))
      (node (ref "DB300") (pin "9") (pinfunction "9_9") (pintype "passive"))
      (node (ref "R304") (pin "1") (pinfunction "1_1") (pintype "passive"))
    )
    (net (code "8") (name "/ECG_RL") (class "Default")
      (node (ref "DB300") (pin "14") (pinfunction "14_14") (pintype "passive"))
      (node (ref "R333") (pin "1") (pinfunction "1_1") (pintype "passive"))
    )
    (net (code "9") (name "/ECG_V1") (class "Default")
      (node (ref "D306") (pin "1") (pinfunction "1_1") (pintype "passive"))
      (node (ref "DB300") (pin "12") (pinfunction "12_12") (pintype "passive"))
      (node (ref "R320") (pin "1") (pinfunction "1_1") (pintype "passive"))
    )
    (net (code "10") (name "/ECG_V2") (class "Default")
      (node (ref "D308") (pin "1") (pinfunction "1_1") (pintype "passive"))
      (node (ref "DB300") (pin "1") (pinfunction "1_1") (pintype "passive"))
      (node (ref "R330") (pin "1") (pinfunction "1_1") (pintype "passive"))
    )
    (net (code "11") (name "/ECG_V3") (class "Default")
      (node (ref "D310") (pin "1") (pinfunction "1_1") (pintype "passive"))
      (node (ref "DB300") (pin "2") (pinfunction "2_2") (pintype "passive"))
      (node (ref "R340") (pin "1") (pinfunction "1_1") (pintype "passive"))
    )
    (net (code "12") (name "/ECG_V4") (class "Default")
      (node (ref "D305") (pin "1") (pinfunction "1_1") (pintype "passive"))
      (node (ref "DB300") (pin "3") (pinfunction "3_3") (pintype "passive"))
      (node (ref "R315") (pin "1") (pinfunction "1_1") (pintype "passive"))
    )
    (net (code "13") (name "/ECG_V5") (class "Default")
      (node (ref "D307") (pin "1") (pinfunction "1_1") (pintype "passive"))
      (node (ref "DB300") (pin "4") (pinfunction "4_4") (pintype "passive"))
      (node (ref "R325") (pin "1") (pinfunction "1_1") (pintype "passive"))
    )
    (net (code "14") (name "/ECG_V6") (class "Default")
      (node (ref "D309") (pin "1") (pinfunction "1_1") (pintype "passive"))
      (node (ref "DB300") (pin "5") (pinfunction "5_5") (pintype "passive"))
      (node (ref "R336") (pin "1") (pinfunction "1_1") (pintype "passive"))
    )
    (net (code "15") (name "/GPIO1") (class "Default")
      (node (ref "U300") (pin "F5") (pinfunction "GPIO1_F5") (pintype "open_collector"))
    )
    (net (code "16") (name "/GPIO2") (class "Default")
      (node (ref "U300") (pin "E7") (pinfunction "GPIO2_E7") (pintype "open_collector"))
    )
    (net (code "17") (name "/GPIO3") (class "Default")
      (node (ref "U300") (pin "E6") (pinfunction "GPIO3_E6") (pintype "open_collector"))
    )
    (net (code "18") (name "/GPIO4") (class "Default")
      (node (ref "U300") (pin "E5") (pinfunction "GPIO4_E5") (pintype "open_collector"))
    )
    (net (code "19") (name "/LA") (class "Default")
      (node (ref "C325") (pin "1") (pinfunction "1_1") (pintype "passive"))
      (node (ref "R307") (pin "2") (pinfunction "2_2") (pintype "passive"))
      (node (ref "U300") (pin "G1") (pinfunction "IN2P_G1") (pintype "open_collector"))
    )
    (net (code "20") (name "/LL") (class "Default")
      (node (ref "C329") (pin "1") (pinfunction "1_1") (pintype "passive"))
      (node (ref "R309") (pin "2") (pinfunction "2_2") (pintype "passive"))
      (node (ref "U300") (pin "F1") (pinfunction "IN3P_F1") (pintype "open_collector"))
    )
    (net (code "21") (name "/PACEO1") (class "Default")
      (node (ref "U300") (pin "E3") (pinfunction "TESTP_PACE_OUT1_E3") (pintype "open_collector"))
    )
    (net (code "22") (name "/PACEO2") (class "Default")
      (node (ref "U300") (pin "F3") (pinfunction "TESTN_PACE_OUT2_F3") (pintype "open_collector"))
    )
    (net (code "23") (name "/RA") (class "Default")
      (node (ref "C322") (pin "1") (pinfunction "1_1") (pintype "passive"))
      (node (ref "R305") (pin "2") (pinfunction "2_2") (pintype "passive"))
      (node (ref "U300") (pin "F2") (pinfunction "IN3N_F2") (pintype "open_collector"))
      (node (ref "U300") (pin "G2") (pinfunction "IN2N_G2") (pintype "open_collector"))
    )
    (net (code "24") (name "/SPI_CLK") (class "Default")
      (node (ref "U300") (pin "F8") (pinfunction "SCLK_F8") (pintype "open_collector"))
    )
    (net (code "25") (name "/SPI_CS") (class "Default")
      (node (ref "R312") (pin "1") (pinfunction "1_1") (pintype "passive"))
      (node (ref "U300") (pin "F7") (pinfunction "~{CS}_F7") (pintype "open_collector"))
    )
    (net (code "26") (name "/SPI_MISO") (class "Default")
      (node (ref "U300") (pin "E8") (pinfunction "DOUT_E8") (pintype "open_collector"))
    )
    (net (code "27") (name "/SPI_MOSI") (class "Default")
      (node (ref "U300") (pin "H8") (pinfunction "DIN_H8") (pintype "open_collector"))
    )
    (net (code "28") (name "/V1") (class "Default")
      (node (ref "C333") (pin "1") (pinfunction "1_1") (pintype "passive"))
      (node (ref "R321") (pin "2") (pinfunction "2_2") (pintype "passive"))
      (node (ref "U300") (pin "A1") (pinfunction "IN8P_A1") (pintype "open_collector"))
    )
    (net (code "29") (name "/V2") (class "Default")
      (node (ref "C337") (pin "1") (pinfunction "1_1") (pintype "passive"))
      (node (ref "R331") (pin "2") (pinfunction "2_2") (pintype "passive"))
      (node (ref "U300") (pin "E1") (pinfunction "IN4P_E1") (pintype "open_collector"))
    )
    (net (code "30") (name "/V3") (class "Default")
      (node (ref "C342") (pin "1") (pinfunction "1_1") (pintype "passive"))
      (node (ref "R341") (pin "2") (pinfunction "2_2") (pintype "passive"))
      (node (ref "U300") (pin "D1") (pinfunction "IN5P_D1") (pintype "open_collector"))
    )
    (net (code "31") (name "/V4") (class "Default")
      (node (ref "C331") (pin "1") (pinfunction "1_1") (pintype "passive"))
      (node (ref "R316") (pin "2") (pinfunction "2_2") (pintype "passive"))
      (node (ref "U300") (pin "C1") (pinfunction "IN6P_C1") (pintype "open_collector"))
    )
    (net (code "32") (name "/V5") (class "Default")
      (node (ref "C335") (pin "1") (pinfunction "1_1") (pintype "passive"))
      (node (ref "R326") (pin "2") (pinfunction "2_2") (pintype "passive"))
      (node (ref "U300") (pin "B1") (pinfunction "IN7P_B1") (pintype "open_collector"))
    )
    (net (code "33") (name "/V6") (class "Default")
      (node (ref "C340") (pin "1") (pinfunction "1_1") (pintype "passive"))
      (node (ref "R337") (pin "2") (pinfunction "2_2") (pintype "passive"))
      (node (ref "U300") (pin "H2") (pinfunction "IN1N_H2") (pintype "open_collector"))
    )
    (net (code "34") (name "/VCAP1") (class "Default")
      (node (ref "C314") (pin "1") (pinfunction "1_1") (pintype "passive"))
      (node (ref "C318") (pin "1") (pinfunction "1_1") (pintype "passive"))
      (node (ref "U300") (pin "H5") (pinfunction "VCAP1_H5") (pintype "open_collector"))
    )
    (net (code "35") (name "/VCAP2") (class "Default")
      (node (ref "C315") (pin "1") (pinfunction "1_1") (pintype "passive"))
      (node (ref "U300") (pin "H6") (pinfunction "VCAP2_H6") (pintype "open_collector"))
    )
    (net (code "36") (name "/VCAP3") (class "Default")
      (node (ref "C316") (pin "1") (pinfunction "1_1") (pintype "passive"))
      (node (ref "U300") (pin "B7") (pinfunction "VCAP3_B7") (pintype "open_collector"))
    )
    (net (code "37") (name "/VCAP4") (class "Default")
      (node (ref "C317") (pin "1") (pinfunction "1_1") (pintype "passive"))
      (node (ref "U300") (pin "G3") (pinfunction "VCAP4_G3") (pintype "open_collector"))
    )
    (net (code "38") (name "/VREFP") (class "Default")
      (node (ref "C326") (pin "1") (pinfunction "1_1") (pintype "passive"))
      (node (ref "C327") (pin "1") (pinfunction "1_1") (pintype "passive"))
      (node (ref "U300") (pin "H3") (pinfunction "VREFP_H3") (pintype "open_collector"))
    )
    (net (code "39") (name "3V3") (class "Default")
      (node (ref "R301") (pin "1") (pinfunction "1_1") (pintype "passive"))
      (node (ref "R302") (pin "1") (pinfunction "1_1") (pintype "passive"))
    )
    (net (code "40") (name "AFE_A") (class "Default")
      (node (ref "C301") (pin "1") (pinfunction "1_1") (pintype "passive"))
      (node (ref "C302") (pin "1") (pinfunction "1_1") (pintype "passive"))
      (node (ref "C303") (pin "1") (pinfunction "1_1") (pintype "passive"))
      (node (ref "C304") (pin "1") (pinfunction "1_1") (pintype "passive"))
      (node (ref "C305") (pin "1") (pinfunction "1_1") (pintype "passive"))
      (node (ref "C311") (pin "1") (pinfunction "1_1") (pintype "passive"))
      (node (ref "C312") (pin "1") (pinfunction "1_1") (pintype "passive"))
      (node (ref "C313") (pin "1") (pinfunction "1_1") (pintype "passive"))
      (node (ref "C320") (pin "1") (pinfunction "1_1") (pintype "passive"))
      (node (ref "D301") (pin "1") (pinfunction "1_1") (pintype "passive"))
      (node (ref "L301") (pin "2") (pinfunction "2_2") (pintype "passive"))
      (node (ref "U300") (pin "A4") (pinfunction "AVDD_2_A4") (pintype "open_collector"))
      (node (ref "U300") (pin "A6") (pinfunction "AVDD_4_A6") (pintype "open_collector"))
      (node (ref "U300") (pin "A7") (pinfunction "AVDD1_A7") (pintype "open_collector"))
      (node (ref "U300") (pin "B4") (pinfunction "AVDD_3_B4") (pintype "open_collector"))
      (node (ref "U300") (pin "B6") (pinfunction "AVDD_5_B6") (pintype "open_collector"))
      (node (ref "U300") (pin "C6") (pinfunction "AVDD_C6") (pintype "open_collector"))
    )
    (net (code "41") (name "AFE_D") (class "Default")
      (node (ref "C300") (pin "1") (pinfunction "1_1") (pintype "passive"))
      (node (ref "C306") (pin "1") (pinfunction "1_1") (pintype "passive"))
      (node (ref "C307") (pin "1") (pinfunction "1_1") (pintype "passive"))
      (node (ref "C308") (pin "1") (pinfunction "1_1") (pintype "passive"))
      (node (ref "C309") (pin "1") (pinfunction "1_1") (pintype "passive"))
      (node (ref "C310") (pin "1") (pinfunction "1_1") (pintype "passive"))
      (node (ref "D300") (pin "1") (pinfunction "1_1") (pintype "passive"))
      (node (ref "L300") (pin "2") (pinfunction "2_2") (pintype "passive"))
      (node (ref "R311") (pin "2") (pinfunction "2_2") (pintype "passive"))
      (node (ref "R312") (pin "2") (pinfunction "2_2") (pintype "passive"))
      (node (ref "R313") (pin "2") (pinfunction "2_2") (pintype "passive"))
      (node (ref "R322") (pin "2") (pinfunction "2_2") (pintype "passive"))
      (node (ref "R324") (pin "2") (pinfunction "2_2") (pintype "passive"))
      (node (ref "R327") (pin "2") (pinfunction "2_2") (pintype "passive"))
      (node (ref "R328") (pin "2") (pinfunction "2_2") (pintype "passive"))
      (node (ref "R338") (pin "1") (pinfunction "1_1") (pintype "passive"))
      (node (ref "U300") (pin "C8") (pinfunction "DVDD_2_C8") (pintype "open_collector"))
      (node (ref "U300") (pin "D8") (pinfunction "DVDD_D8") (pintype "open_collector"))
      (node (ref "XT300") (pin "4") (pinfunction "VCC_4") (pintype "passive"))
    )
    (net (code "42") (name "AGND") (class "Default")
      (node (ref "C300") (pin "2") (pinfunction "2_2") (pintype "passive"))
      (node (ref "C301") (pin "2") (pinfunction "2_2") (pintype "passive"))
      (node (ref "C302") (pin "2") (pinfunction "2_2") (pintype "passive"))
      (node (ref "C303") (pin "2") (pinfunction "2_2") (pintype "passive"))
      (node (ref "C304") (pin "2") (pinfunction "2_2") (pintype "passive"))
      (node (ref "C305") (pin "2") (pinfunction "2_2") (pintype "passive"))
      (node (ref "C306") (pin "2") (pinfunction "2_2") (pintype "passive"))
      (node (ref "C307") (pin "2") (pinfunction "2_2") (pintype "passive"))
      (node (ref "C308") (pin "2") (pinfunction "2_2") (pintype "passive"))
      (node (ref "C309") (pin "2") (pinfunction "2_2") (pintype "passive"))
      (node (ref "C310") (pin "2") (pinfunction "2_2") (pintype "passive"))
      (node (ref "C311") (pin "2") (pinfunction "2_2") (pintype "passive"))
      (node (ref "C312") (pin "2") (pinfunction "2_2") (pintype "passive"))
      (node (ref "C313") (pin "2") (pinfunction "2_2") (pintype "passive"))
      (node (ref "C314") (pin "2") (pinfunction "2_2") (pintype "passive"))
      (node (ref "C315") (pin "2") (pinfunction "2_2") (pintype "passive"))
      (node (ref "C316") (pin "2") (pinfunction "2_2") (pintype "passive"))
      (node (ref "C317") (pin "2") (pinfunction "2_2") (pintype "passive"))
      (node (ref "C318") (pin "2") (pinfunction "2_2") (pintype "passive"))
      (node (ref "C319") (pin "2") (pinfunction "2_2") (pintype "passive"))
      (node (ref "C320") (pin "2") (pinfunction "2_2") (pintype "passive"))
      (node (ref "C321") (pin "2") (pinfunction "2_2") (pintype "passive"))
      (node (ref "C322") (pin "2") (pinfunction "2_2") (pintype "passive"))
      (node (ref "C323") (pin "1") (pinfunction "1_1") (pintype "passive"))
      (node (ref "C324") (pin "2") (pinfunction "2_2") (pintype "passive"))
      (node (ref "C325") (pin "2") (pinfunction "2_2") (pintype "passive"))
      (node (ref "C326") (pin "2") (pinfunction "2_2") (pintype "passive"))
      (node (ref "C327") (pin "2") (pinfunction "2_2") (pintype "passive"))
      (node (ref "C328") (pin "2") (pinfunction "2_2") (pintype "passive"))
      (node (ref "C329") (pin "2") (pinfunction "2_2") (pintype "passive"))
      (node (ref "C330") (pin "2") (pinfunction "2_2") (pintype "passive"))
      (node (ref "C331") (pin "2") (pinfunction "2_2") (pintype "passive"))
      (node (ref "C332") (pin "2") (pinfunction "2_2") (pintype "passive"))
      (node (ref "C333") (pin "2") (pinfunction "2_2") (pintype "passive"))
      (node (ref "C334") (pin "2") (pinfunction "2_2") (pintype "passive"))
      (node (ref "C335") (pin "2") (pinfunction "2_2") (pintype "passive"))
      (node (ref "C336") (pin "2") (pinfunction "2_2") (pintype "passive"))
      (node (ref "C337") (pin "2") (pinfunction "2_2") (pintype "passive"))
      (node (ref "C339") (pin "2") (pinfunction "2_2") (pintype "passive"))
      (node (ref "C340") (pin "2") (pinfunction "2_2") (pintype "passive"))
      (node (ref "C341") (pin "2") (pinfunction "2_2") (pintype "passive"))
      (node (ref "C342") (pin "2") (pinfunction "2_2") (pintype "passive"))
      (node (ref "D300") (pin "2") (pinfunction "2_2") (pintype "passive"))
      (node (ref "D301") (pin "2") (pinfunction "2_2") (pintype "passive"))
      (node (ref "D302") (pin "2") (pinfunction "2_2") (pintype "passive"))
      (node (ref "D303") (pin "2") (pinfunction "2_2") (pintype "passive"))
      (node (ref "D304") (pin "2") (pinfunction "2_2") (pintype "passive"))
      (node (ref "D305") (pin "2") (pinfunction "2_2") (pintype "passive"))
      (node (ref "D306") (pin "2") (pinfunction "2_2") (pintype "passive"))
      (node (ref "D307") (pin "2") (pinfunction "2_2") (pintype "passive"))
      (node (ref "D308") (pin "2") (pinfunction "2_2") (pintype "passive"))
      (node (ref "D309") (pin "2") (pinfunction "2_2") (pintype "passive"))
      (node (ref "D310") (pin "2") (pinfunction "2_2") (pintype "passive"))
      (node (ref "DB300") (pin "6") (pinfunction "6_6") (pintype "passive"))
      (node (ref "R303") (pin "2") (pinfunction "2_2") (pintype "passive"))
      (node (ref "R318") (pin "1") (pinfunction "1_1") (pintype "passive"))
      (node (ref "R339") (pin "2") (pinfunction "2_2") (pintype "passive"))
      (node (ref "U300") (pin "A5") (pinfunction "AVSS_3_A5") (pintype "open_collector"))
      (node (ref "U300") (pin "A8") (pinfunction "AVSS1_A8") (pintype "open_collector"))
      (node (ref "U300") (pin "B5") (pinfunction "AVSS_4_B5") (pintype "open_collector"))
      (node (ref "U300") (pin "C5") (pinfunction "AVSS_5_C5") (pintype "open_collector"))
      (node (ref "U300") (pin "C7") (pinfunction "DGND_2_C7") (pintype "open_collector"))
      (node (ref "U300") (pin "D4") (pinfunction "AVSS_2_D4") (pintype "open_collector"))
      (node (ref "U300") (pin "D5") (pinfunction "AVSS_D5") (pintype "open_collector"))
      (node (ref "U300") (pin "D7") (pinfunction "DGND_3_D7") (pintype "open_collector"))
      (node (ref "U300") (pin "E4") (pinfunction "RESV1_E4") (pintype "open_collector"))
      (node (ref "U300") (pin "F6") (pinfunction "DAISY_IN_F6") (pintype "open_collector"))
      (node (ref "U300") (pin "H4") (pinfunction "VREFN_H4") (pintype "open_collector"))
      (node (ref "U300") (pin "H7") (pinfunction "DGND_H7") (pintype "open_collector"))
      (node (ref "XT300") (pin "2") (pinfunction "2_2") (pintype "passive"))
    )
    (net (code "43") (name "GND") (class "Default")
      (node (ref "R303") (pin "1") (pinfunction "1_1") (pintype "passive"))
    )
    (net (code "44") (name "Net-(C319-Pad1)") (class "Default")
      (node (ref "C319") (pin "1") (pinfunction "1_1") (pintype "passive"))
      (node (ref "L301") (pin "1") (pinfunction "1_1") (pintype "passive"))
      (node (ref "R302") (pin "2") (pinfunction "2_2") (pintype "passive"))
    )
    (net (code "45") (name "Net-(C321-Pad1)") (class "Default")
      (node (ref "C321") (pin "1") (pinfunction "1_1") (pintype "passive"))
      (node (ref "R304") (pin "2") (pinfunction "2_2") (pintype "passive"))
      (node (ref "R305") (pin "1") (pinfunction "1_1") (pintype "passive"))
    )
    (net (code "46") (name "Net-(C324-Pad1)") (class "Default")
      (node (ref "C324") (pin "1") (pinfunction "1_1") (pintype "passive"))
      (node (ref "R306") (pin "2") (pinfunction "2_2") (pintype "passive"))
      (node (ref "R307") (pin "1") (pinfunction "1_1") (pintype "passive"))
    )
    (net (code "47") (name "Net-(C328-Pad1)") (class "Default")
      (node (ref "C328") (pin "1") (pinfunction "1_1") (pintype "passive"))
      (node (ref "R308") (pin "2") (pinfunction "2_2") (pintype "passive"))
      (node (ref "R309") (pin "1") (pinfunction "1_1") (pintype "passive"))
    )
    (net (code "48") (name "Net-(C330-Pad1)") (class "Default")
      (node (ref "C330") (pin "1") (pinfunction "1_1") (pintype "passive"))
      (node (ref "R315") (pin "2") (pinfunction "2_2") (pintype "passive"))
      (node (ref "R316") (pin "1") (pinfunction "1_1") (pintype "passive"))
    )
    (net (code "49") (name "Net-(C332-Pad1)") (class "Default")
      (node (ref "C332") (pin "1") (pinfunction "1_1") (pintype "passive"))
      (node (ref "R320") (pin "2") (pinfunction "2_2") (pintype "passive"))
      (node (ref "R321") (pin "1") (pinfunction "1_1") (pintype "passive"))
    )
    (net (code "50") (name "Net-(C334-Pad1)") (class "Default")
      (node (ref "C334") (pin "1") (pinfunction "1_1") (pintype "passive"))
      (node (ref "R325") (pin "2") (pinfunction "2_2") (pintype "passive"))
      (node (ref "R326") (pin "1") (pinfunction "1_1") (pintype "passive"))
    )
    (net (code "51") (name "Net-(C336-Pad1)") (class "Default")
      (node (ref "C336") (pin "1") (pinfunction "1_1") (pintype "passive"))
      (node (ref "R330") (pin "2") (pinfunction "2_2") (pintype "passive"))
      (node (ref "R331") (pin "1") (pinfunction "1_1") (pintype "passive"))
    )
    (net (code "52") (name "Net-(C339-Pad1)") (class "Default")
      (node (ref "C339") (pin "1") (pinfunction "1_1") (pintype "passive"))
      (node (ref "R336") (pin "2") (pinfunction "2_2") (pintype "passive"))
      (node (ref "R337") (pin "1") (pinfunction "1_1") (pintype "passive"))
    )
    (net (code "53") (name "Net-(C341-Pad1)") (class "Default")
      (node (ref "C341") (pin "1") (pinfunction "1_1") (pintype "passive"))
      (node (ref "R340") (pin "2") (pinfunction "2_2") (pintype "passive"))
      (node (ref "R341") (pin "1") (pinfunction "1_1") (pintype "passive"))
    )
    (net (code "54") (name "Net-(L300-Pad1)") (class "Default")
      (node (ref "L300") (pin "1") (pinfunction "1_1") (pintype "passive"))
      (node (ref "R301") (pin "2") (pinfunction "2_2") (pintype "passive"))
    )
    (net (code "55") (name "Net-(R324-Pad1)") (class "Default")
      (node (ref "R324") (pin "1") (pinfunction "1_1") (pintype "passive"))
      (node (ref "XT300") (pin "1") (pinfunction "1_1") (pintype "passive"))
    )
    (net (code "56") (name "Net-(R335-Pad1)") (class "Default")
      (node (ref "R335") (pin "1") (pinfunction "1_1") (pintype "passive"))
      (node (ref "R338") (pin "2") (pinfunction "2_2") (pintype "passive"))
      (node (ref "R339") (pin "1") (pinfunction "1_1") (pintype "passive"))
    )
    (net (code "57") (name "Net-(U300A-IN1P)") (class "Default")
      (node (ref "R329") (pin "2") (pinfunction "2_2") (pintype "passive"))
      (node (ref "U300") (pin "H1") (pinfunction "IN1P_H1") (pintype "open_collector"))
    )
    (net (code "58") (name "Net-(U300A-IN4N)") (class "Default")
      (node (ref "R323") (pin "2") (pinfunction "2_2") (pintype "passive"))
      (node (ref "U300") (pin "E2") (pinfunction "IN4N_E2") (pintype "open_collector"))
    )
    (net (code "59") (name "Net-(U300A-IN5N)") (class "Default")
      (node (ref "R319") (pin "2") (pinfunction "2_2") (pintype "passive"))
      (node (ref "U300") (pin "D2") (pinfunction "IN5N_D2") (pintype "open_collector"))
    )
    (net (code "60") (name "Net-(U300A-IN6N)") (class "Default")
      (node (ref "R317") (pin "2") (pinfunction "2_2") (pintype "passive"))
      (node (ref "U300") (pin "C2") (pinfunction "IN6N_C2") (pintype "open_collector"))
    )
    (net (code "61") (name "Net-(U300A-IN7N)") (class "Default")
      (node (ref "R314") (pin "2") (pinfunction "2_2") (pintype "passive"))
      (node (ref "U300") (pin "B2") (pinfunction "IN7N_B2") (pintype "open_collector"))
    )
    (net (code "62") (name "Net-(U300A-IN8N)") (class "Default")
      (node (ref "R310") (pin "2") (pinfunction "2_2") (pintype "passive"))
      (node (ref "U300") (pin "A2") (pinfunction "IN8N_A2") (pintype "open_collector"))
    )
    (net (code "63") (name "Net-(U300A-RLDIN)") (class "Default")
      (node (ref "C338") (pin "1") (pinfunction "1_1") (pintype "passive"))
      (node (ref "R332") (pin "2") (pinfunction "2_2") (pintype "passive"))
      (node (ref "U300") (pin "A3") (pinfunction "RLDIN_A3") (pintype "open_collector"))
    )
    (net (code "64") (name "Net-(U300A-RLDINV)") (class "Default")
      (node (ref "C338") (pin "2") (pinfunction "2_2") (pintype "passive"))
      (node (ref "R332") (pin "1") (pinfunction "1_1") (pintype "passive"))
      (node (ref "R333") (pin "2") (pinfunction "2_2") (pintype "passive"))
      (node (ref "R334") (pin "1") (pinfunction "1_1") (pintype "passive"))
      (node (ref "U300") (pin "C3") (pinfunction "RLDINV_C3") (pintype "open_collector"))
    )
    (net (code "65") (name "Net-(U300A-RLDOUT)") (class "Default")
      (node (ref "R334") (pin "2") (pinfunction "2_2") (pintype "passive"))
      (node (ref "U300") (pin "B3") (pinfunction "RLDOUT_B3") (pintype "open_collector"))
    )
    (net (code "66") (name "Net-(U300A-RLDREF)") (class "Default")
      (node (ref "R335") (pin "2") (pinfunction "2_2") (pintype "passive"))
      (node (ref "U300") (pin "C4") (pinfunction "RLDREF_C4") (pintype "open_collector"))
    )
    (net (code "67") (name "Net-(U300A-START)") (class "Default")
      (node (ref "R322") (pin "1") (pinfunction "1_1") (pintype "passive"))
      (node (ref "U300") (pin "G7") (pinfunction "START_G7") (pintype "open_collector"))
    )
    (net (code "68") (name "Net-(U300A-WCT)") (class "Default")
      (node (ref "C323") (pin "2") (pinfunction "2_2") (pintype "passive"))
      (node (ref "R310") (pin "1") (pinfunction "1_1") (pintype "passive"))
      (node (ref "R314") (pin "1") (pinfunction "1_1") (pintype "passive"))
      (node (ref "R317") (pin "1") (pinfunction "1_1") (pintype "passive"))
      (node (ref "R319") (pin "1") (pinfunction "1_1") (pintype "passive"))
      (node (ref "R323") (pin "1") (pinfunction "1_1") (pintype "passive"))
      (node (ref "R329") (pin "1") (pinfunction "1_1") (pintype "passive"))
      (node (ref "U300") (pin "D3") (pinfunction "WCT_D3") (pintype "open_collector"))
    )
    (net (code "69") (name "Net-(U300A-~{PWDN})") (class "Default")
      (node (ref "R328") (pin "1") (pinfunction "1_1") (pintype "passive"))
      (node (ref "U300") (pin "G5") (pinfunction "~{PWDN}_G5") (pintype "open_collector"))
    )
    (net (code "70") (name "Net-(U300A-~{RESET})") (class "Default")
      (node (ref "R327") (pin "1") (pinfunction "1_1") (pintype "passive"))
      (node (ref "U300") (pin "G6") (pinfunction "~{RESET}_G6") (pintype "open_collector"))
    )
    (net (code "71") (name "unconnected-(DB300-Pad7)") (class "Default")
      (node (ref "DB300") (pin "7") (pinfunction "7_7") (pintype "passive+no_connect"))
    )
    (net (code "72") (name "unconnected-(DB300-Pad8)") (class "Default")
      (node (ref "DB300") (pin "8") (pinfunction "8_8") (pintype "passive+no_connect"))
    )
    (net (code "73") (name "unconnected-(DB300-Pad13)") (class "Default")
      (node (ref "DB300") (pin "13") (pinfunction "13_13") (pintype "passive+no_connect"))
    )
    (net (code "74") (name "unconnected-(DB300-Pad15)") (class "Default")
      (node (ref "DB300") (pin "15") (pinfunction "15_15") (pintype "passive+no_connect"))
    )
    (net (code "75") (name "unconnected-(U300A-RESP_MODN-PadF4)") (class "Default")
      (node (ref "U300") (pin "F4") (pinfunction "RESP_MODN_F4") (pintype "open_collector+no_connect"))
    )
    (net (code "76") (name "unconnected-(U300B-RESV3-PadG4)") (class "Default")
      (node (ref "U300") (pin "G4") (pinfunction "RESV3_G4") (pintype "open_collector+no_connect"))
    )
  )
)
